# I2C_motor_driver.net
KiCad netlist of a schematic drawn in EAGLE
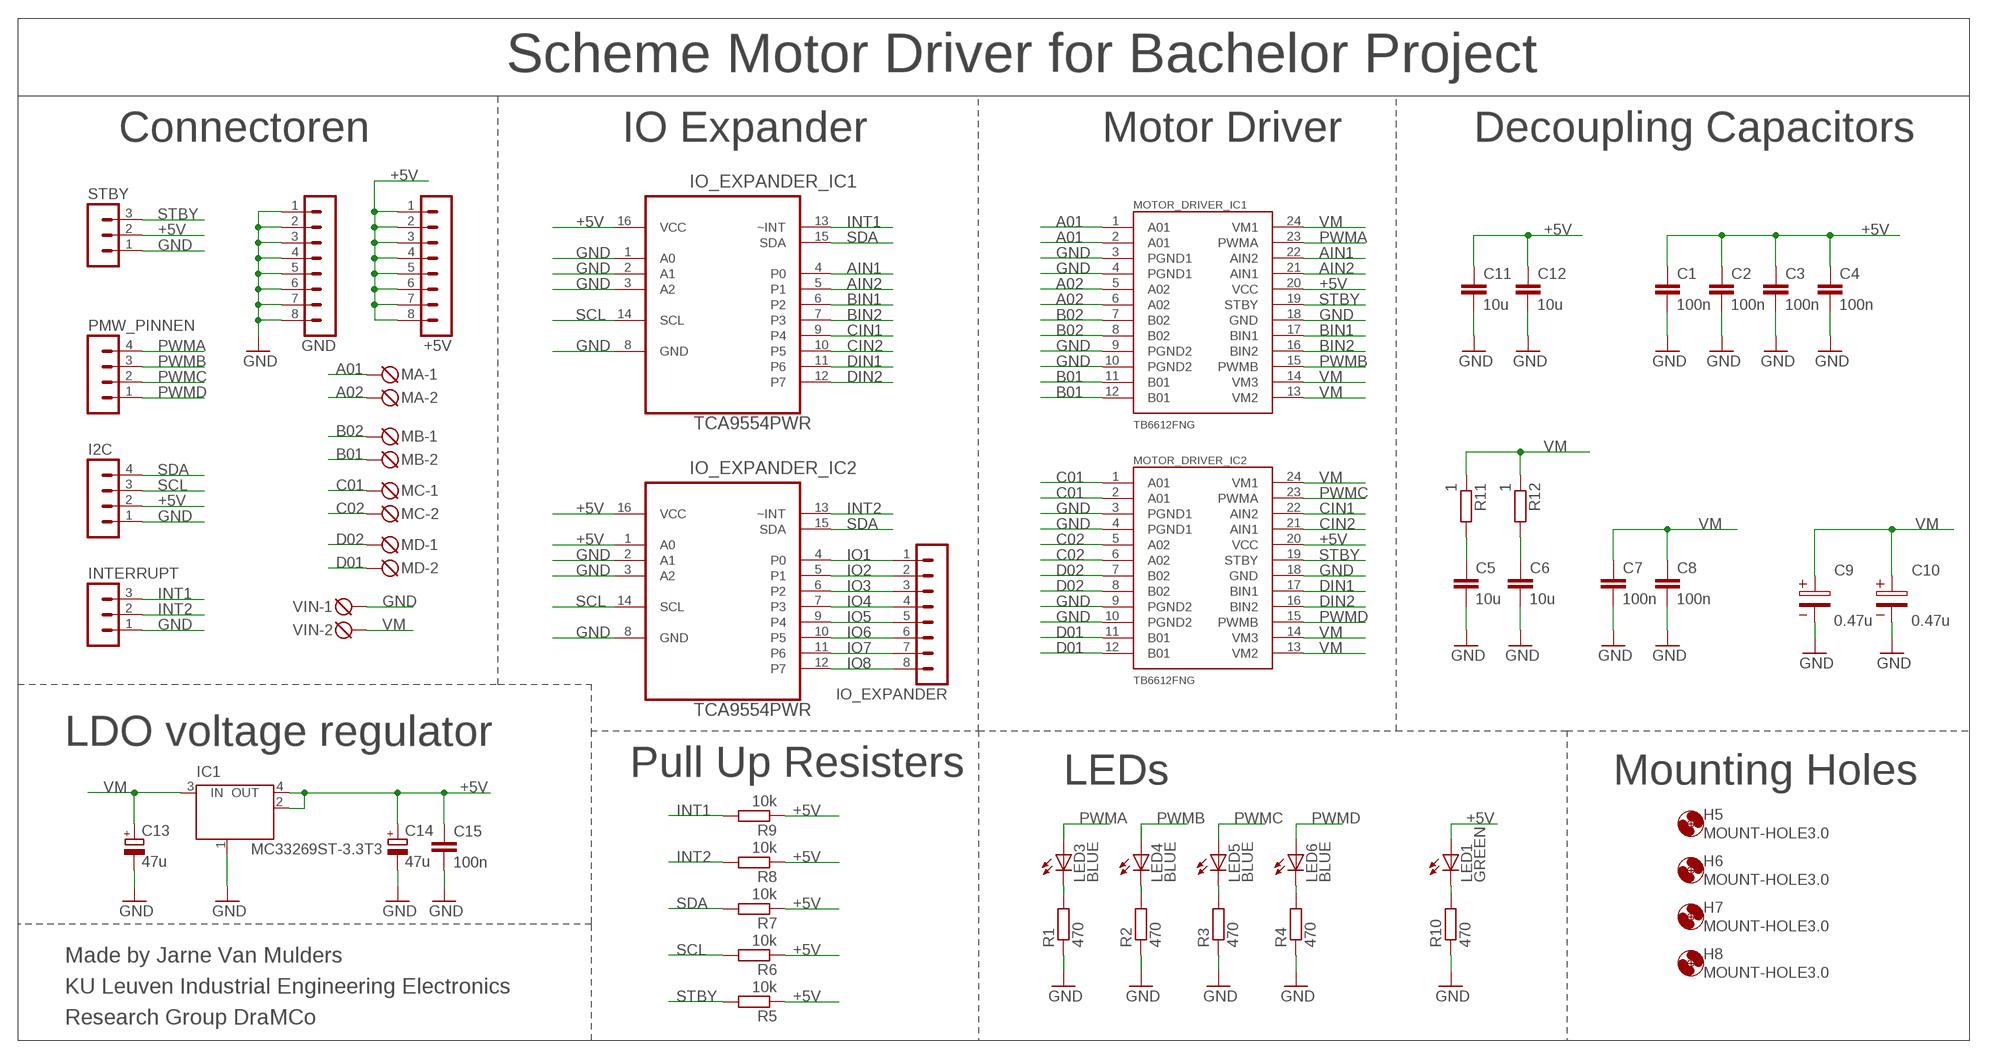
[diagram p0: schematic, sheet 1]

(export (version "E")
  (design (tool "Eeschema 10.0.6"))
  (components
    (comp (ref "+5V")
      (value "MA08-1")
      (footprint "eagle-import:MA08-1")
      (libsource (lib "eagle-import") (part "MA08-1"))
    )
    (comp (ref "C1")
      (value "100n")
      (footprint "eagle-import:C1206K")
      (libsource (lib "eagle-import") (part "C-EUC1206K"))
    )
    (comp (ref "C2")
      (value "100n")
      (footprint "eagle-import:C1206K")
      (libsource (lib "eagle-import") (part "C-EUC1206K"))
    )
    (comp (ref "C3")
      (value "100n")
      (footprint "eagle-import:C1206K")
      (libsource (lib "eagle-import") (part "C-EUC1206K"))
    )
    (comp (ref "C4")
      (value "100n")
      (footprint "eagle-import:C1206K")
      (libsource (lib "eagle-import") (part "C-EUC1206K"))
    )
    (comp (ref "C5")
      (value "10u")
      (footprint "eagle-import:C1206K")
      (libsource (lib "eagle-import") (part "C-EUC1206K"))
    )
    (comp (ref "C6")
      (value "10u")
      (footprint "eagle-import:C1206K")
      (libsource (lib "eagle-import") (part "C-EUC1206K"))
    )
    (comp (ref "C7")
      (value "100n")
      (footprint "eagle-import:C1206K")
      (libsource (lib "eagle-import") (part "C-EUC1206K"))
    )
    (comp (ref "C8")
      (value "100n")
      (footprint "eagle-import:C1206K")
      (libsource (lib "eagle-import") (part "C-EUC1206K"))
    )
    (comp (ref "C9")
      (value "0.47u")
      (footprint "eagle-import:2.6X1.6X1(BXCXA)")
      (libsource (lib "eagle-import") (part "WCAP-ASLI_865080740002_4X5,5"))
    )
    (comp (ref "C10")
      (value "0.47u")
      (footprint "eagle-import:2.6X1.6X1(BXCXA)")
      (libsource (lib "eagle-import") (part "WCAP-ASLI_865080740002_4X5,5"))
    )
    (comp (ref "C11")
      (value "10u")
      (footprint "eagle-import:C1206K")
      (libsource (lib "eagle-import") (part "C-EUC1206K"))
    )
    (comp (ref "C12")
      (value "10u")
      (footprint "eagle-import:C1206K")
      (libsource (lib "eagle-import") (part "C-EUC1206K"))
    )
    (comp (ref "C13")
      (value "47u")
      (footprint "eagle-import:PANASONIC_D")
      (libsource (lib "eagle-import") (part "CPOL-EUD"))
    )
    (comp (ref "C14")
      (value "47u")
      (footprint "eagle-import:PANASONIC_D")
      (libsource (lib "eagle-import") (part "CPOL-EUD"))
    )
    (comp (ref "C15")
      (value "100n")
      (footprint "eagle-import:C1206K")
      (libsource (lib "eagle-import") (part "C-EUC1206K"))
    )
    (comp (ref "GND")
      (value "MA08-1")
      (footprint "eagle-import:MA08-1")
      (libsource (lib "eagle-import") (part "MA08-1"))
    )
    (comp (ref "H5")
      (value "MOUNT-HOLE3.0")
      (footprint "eagle-import:3,0")
      (libsource (lib "eagle-import") (part "MOUNT-HOLE3.0"))
    )
    (comp (ref "H6")
      (value "MOUNT-HOLE3.0")
      (footprint "eagle-import:3,0")
      (libsource (lib "eagle-import") (part "MOUNT-HOLE3.0"))
    )
    (comp (ref "H7")
      (value "MOUNT-HOLE3.0")
      (footprint "eagle-import:3,0")
      (libsource (lib "eagle-import") (part "MOUNT-HOLE3.0"))
    )
    (comp (ref "H8")
      (value "MOUNT-HOLE3.0")
      (footprint "eagle-import:3,0")
      (libsource (lib "eagle-import") (part "MOUNT-HOLE3.0"))
    )
    (comp (ref "I2C")
      (value "MA04-1")
      (footprint "eagle-import:MA04-1")
      (libsource (lib "eagle-import") (part "MA04-1"))
    )
    (comp (ref "IC1")
      (value "MC33269ST-3.3T3")
      (footprint "eagle-import:SOT223")
      (libsource (lib "eagle-import") (part "MC33269ST-3.3T3"))
    )
    (comp (ref "INTERRUPT")
      (value "MA03-1")
      (footprint "eagle-import:MA03-1")
      (libsource (lib "eagle-import") (part "MA03-1"))
    )
    (comp (ref "IO_EXPANDER")
      (value "MA08-1")
      (footprint "eagle-import:MA08-1")
      (libsource (lib "eagle-import") (part "MA08-1"))
    )
    (comp (ref "IO_EXPANDER_IC1")
      (value "TCA9554PWR")
      (footprint "eagle-import:SOP65P640X120-16N")
      (fields (field (name "MF") "Texas Instruments"))
      (libsource (lib "eagle-import") (part "TCA9554PWR"))
    )
    (comp (ref "IO_EXPANDER_IC2")
      (value "TCA9554PWR")
      (footprint "eagle-import:SOP65P640X120-16N")
      (fields (field (name "MF") "Texas Instruments"))
      (libsource (lib "eagle-import") (part "TCA9554PWR"))
    )
    (comp (ref "LED1")
      (value "GREEN")
      (footprint "eagle-import:SML0805")
      (libsource (lib "eagle-import") (part "LEDSML0805"))
    )
    (comp (ref "LED3")
      (value "BLUE")
      (footprint "eagle-import:SML0805")
      (libsource (lib "eagle-import") (part "LEDSML0805"))
    )
    (comp (ref "LED4")
      (value "BLUE")
      (footprint "eagle-import:SML0805")
      (libsource (lib "eagle-import") (part "LEDSML0805"))
    )
    (comp (ref "LED5")
      (value "BLUE")
      (footprint "eagle-import:SML0805")
      (libsource (lib "eagle-import") (part "LEDSML0805"))
    )
    (comp (ref "LED6")
      (value "BLUE")
      (footprint "eagle-import:SML0805")
      (libsource (lib "eagle-import") (part "LEDSML0805"))
    )
    (comp (ref "MA")
      (value "DG3XX-02-5.0")
      (footprint "eagle-import:DG306-5.0-02P")
      (libsource (lib "eagle-import") (part "DG3XX-02-5.0"))
    )
    (comp (ref "MB")
      (value "DG3XX-02-5.0")
      (footprint "eagle-import:DG306-5.0-02P")
      (libsource (lib "eagle-import") (part "DG3XX-02-5.0"))
    )
    (comp (ref "MC")
      (value "DG3XX-02-5.0")
      (footprint "eagle-import:DG306-5.0-02P")
      (libsource (lib "eagle-import") (part "DG3XX-02-5.0"))
    )
    (comp (ref "MD")
      (value "DG3XX-02-5.0")
      (footprint "eagle-import:DG306-5.0-02P")
      (libsource (lib "eagle-import") (part "DG3XX-02-5.0"))
    )
    (comp (ref "MOTOR_DRIVER_IC1")
      (value "TB6612FNG")
      (footprint "eagle-import:SSOP24")
      (libsource (lib "eagle-import") (part "TB6612FNG"))
    )
    (comp (ref "MOTOR_DRIVER_IC2")
      (value "TB6612FNG")
      (footprint "eagle-import:SSOP24")
      (libsource (lib "eagle-import") (part "TB6612FNG"))
    )
    (comp (ref "PMW_PINNEN")
      (value "MA04-1")
      (footprint "eagle-import:MA04-1")
      (libsource (lib "eagle-import") (part "MA04-1"))
    )
    (comp (ref "R1")
      (value "470")
      (footprint "eagle-import:R1206")
      (libsource (lib "eagle-import") (part "R-EU_R1206"))
    )
    (comp (ref "R2")
      (value "470")
      (footprint "eagle-import:R1206")
      (libsource (lib "eagle-import") (part "R-EU_R1206"))
    )
    (comp (ref "R3")
      (value "470")
      (footprint "eagle-import:R1206")
      (libsource (lib "eagle-import") (part "R-EU_R1206"))
    )
    (comp (ref "R4")
      (value "470")
      (footprint "eagle-import:R1206")
      (libsource (lib "eagle-import") (part "R-EU_R1206"))
    )
    (comp (ref "R5")
      (value "10k")
      (footprint "eagle-import:R1206")
      (libsource (lib "eagle-import") (part "R-EU_R1206"))
    )
    (comp (ref "R6")
      (value "10k")
      (footprint "eagle-import:R1206")
      (libsource (lib "eagle-import") (part "R-EU_R1206"))
    )
    (comp (ref "R7")
      (value "10k")
      (footprint "eagle-import:R1206")
      (libsource (lib "eagle-import") (part "R-EU_R1206"))
    )
    (comp (ref "R8")
      (value "10k")
      (footprint "eagle-import:R1206")
      (libsource (lib "eagle-import") (part "R-EU_R1206"))
    )
    (comp (ref "R9")
      (value "10k")
      (footprint "eagle-import:R1206")
      (libsource (lib "eagle-import") (part "R-EU_R1206"))
    )
    (comp (ref "R10")
      (value "470")
      (footprint "eagle-import:R1206")
      (libsource (lib "eagle-import") (part "R-EU_R1206"))
    )
    (comp (ref "R11")
      (value "1")
      (footprint "eagle-import:R1206")
      (libsource (lib "eagle-import") (part "R-EU_R1206"))
    )
    (comp (ref "R12")
      (value "1")
      (footprint "eagle-import:R1206")
      (libsource (lib "eagle-import") (part "R-EU_R1206"))
    )
    (comp (ref "STBY")
      (value "MA03-1")
      (footprint "eagle-import:MA03-1")
      (libsource (lib "eagle-import") (part "MA03-1"))
    )
    (comp (ref "VIN")
      (value "DG3XX-02-5.0")
      (footprint "eagle-import:DG306-5.0-02P")
      (libsource (lib "eagle-import") (part "DG3XX-02-5.0"))
    )
  )
  (nets
    (net (code "1") (name "/+5V") (class "Default")
      (node (ref "+5V") (pin "1") (pinfunction "1_1") (pintype "passive"))
      (node (ref "+5V") (pin "2") (pinfunction "2_2") (pintype "passive"))
      (node (ref "+5V") (pin "3") (pinfunction "3_3") (pintype "passive"))
      (node (ref "+5V") (pin "4") (pinfunction "4_4") (pintype "passive"))
      (node (ref "+5V") (pin "5") (pinfunction "5_5") (pintype "passive"))
      (node (ref "+5V") (pin "6") (pinfunction "6_6") (pintype "passive"))
      (node (ref "+5V") (pin "7") (pinfunction "7_7") (pintype "passive"))
      (node (ref "+5V") (pin "8") (pinfunction "8_8") (pintype "passive"))
      (node (ref "C1") (pin "1") (pinfunction "1_1") (pintype "passive"))
      (node (ref "C11") (pin "1") (pinfunction "1_1") (pintype "passive"))
      (node (ref "C12") (pin "1") (pinfunction "1_1") (pintype "passive"))
      (node (ref "C14") (pin "+") (pinfunction "+_+") (pintype "passive"))
      (node (ref "C15") (pin "1") (pinfunction "1_1") (pintype "passive"))
      (node (ref "C2") (pin "1") (pinfunction "1_1") (pintype "passive"))
      (node (ref "C3") (pin "1") (pinfunction "1_1") (pintype "passive"))
      (node (ref "C4") (pin "1") (pinfunction "1_1") (pintype "passive"))
      (node (ref "I2C") (pin "2") (pinfunction "2_2") (pintype "passive"))
      (node (ref "IC1") (pin "2") (pinfunction "OUT_2") (pintype "passive"))
      (node (ref "IC1") (pin "4") (pinfunction "OUT_4") (pintype "passive"))
      (node (ref "IO_EXPANDER_IC1") (pin "16") (pinfunction "VCC_16") (pintype "power_in"))
      (node (ref "IO_EXPANDER_IC2") (pin "1") (pinfunction "A0_1") (pintype "input"))
      (node (ref "IO_EXPANDER_IC2") (pin "16") (pinfunction "VCC_16") (pintype "power_in"))
      (node (ref "LED1") (pin "A") (pinfunction "A_A") (pintype "passive"))
      (node (ref "MOTOR_DRIVER_IC1") (pin "20") (pinfunction "VCC_20") (pintype "bidirectional"))
      (node (ref "MOTOR_DRIVER_IC2") (pin "20") (pinfunction "VCC_20") (pintype "bidirectional"))
      (node (ref "R5") (pin "1") (pinfunction "1_1") (pintype "passive"))
      (node (ref "R6") (pin "1") (pinfunction "1_1") (pintype "passive"))
      (node (ref "R7") (pin "1") (pinfunction "1_1") (pintype "passive"))
      (node (ref "R8") (pin "1") (pinfunction "1_1") (pintype "passive"))
      (node (ref "R9") (pin "1") (pinfunction "1_1") (pintype "passive"))
      (node (ref "STBY") (pin "2") (pinfunction "2_2") (pintype "passive"))
    )
    (net (code "2") (name "/A01") (class "Default")
      (node (ref "MA") (pin "1") (pinfunction "KL_1") (pintype "passive"))
      (node (ref "MOTOR_DRIVER_IC1") (pin "1") (pinfunction "A01_1") (pintype "bidirectional"))
      (node (ref "MOTOR_DRIVER_IC1") (pin "2") (pinfunction "A01_2") (pintype "bidirectional"))
    )
    (net (code "3") (name "/A02") (class "Default")
      (node (ref "MA") (pin "2") (pinfunction "KL_2") (pintype "passive"))
      (node (ref "MOTOR_DRIVER_IC1") (pin "5") (pinfunction "A02_5") (pintype "bidirectional"))
      (node (ref "MOTOR_DRIVER_IC1") (pin "6") (pinfunction "A02_6") (pintype "bidirectional"))
    )
    (net (code "4") (name "/AIN1") (class "Default")
      (node (ref "IO_EXPANDER_IC1") (pin "4") (pinfunction "P0_4") (pintype "bidirectional"))
      (node (ref "MOTOR_DRIVER_IC1") (pin "22") (pinfunction "AIN2_22") (pintype "bidirectional"))
    )
    (net (code "5") (name "/AIN2") (class "Default")
      (node (ref "IO_EXPANDER_IC1") (pin "5") (pinfunction "P1_5") (pintype "bidirectional"))
      (node (ref "MOTOR_DRIVER_IC1") (pin "21") (pinfunction "AIN1_21") (pintype "bidirectional"))
    )
    (net (code "6") (name "/B01") (class "Default")
      (node (ref "MB") (pin "2") (pinfunction "KL_2") (pintype "passive"))
      (node (ref "MOTOR_DRIVER_IC1") (pin "11") (pinfunction "B01_11") (pintype "bidirectional"))
      (node (ref "MOTOR_DRIVER_IC1") (pin "12") (pinfunction "B01_12") (pintype "bidirectional"))
    )
    (net (code "7") (name "/B02") (class "Default")
      (node (ref "MB") (pin "1") (pinfunction "KL_1") (pintype "passive"))
      (node (ref "MOTOR_DRIVER_IC1") (pin "7") (pinfunction "B02_7") (pintype "bidirectional"))
      (node (ref "MOTOR_DRIVER_IC1") (pin "8") (pinfunction "B02_8") (pintype "bidirectional"))
    )
    (net (code "8") (name "/BIN1") (class "Default")
      (node (ref "IO_EXPANDER_IC1") (pin "6") (pinfunction "P2_6") (pintype "bidirectional"))
      (node (ref "MOTOR_DRIVER_IC1") (pin "17") (pinfunction "BIN1_17") (pintype "bidirectional"))
    )
    (net (code "9") (name "/BIN2") (class "Default")
      (node (ref "IO_EXPANDER_IC1") (pin "7") (pinfunction "P3_7") (pintype "bidirectional"))
      (node (ref "MOTOR_DRIVER_IC1") (pin "16") (pinfunction "BIN2_16") (pintype "bidirectional"))
    )
    (net (code "10") (name "/C01") (class "Default")
      (node (ref "MC") (pin "1") (pinfunction "KL_1") (pintype "passive"))
      (node (ref "MOTOR_DRIVER_IC2") (pin "1") (pinfunction "A01_1") (pintype "bidirectional"))
      (node (ref "MOTOR_DRIVER_IC2") (pin "2") (pinfunction "A01_2") (pintype "bidirectional"))
    )
    (net (code "11") (name "/C02") (class "Default")
      (node (ref "MC") (pin "2") (pinfunction "KL_2") (pintype "passive"))
      (node (ref "MOTOR_DRIVER_IC2") (pin "5") (pinfunction "A02_5") (pintype "bidirectional"))
      (node (ref "MOTOR_DRIVER_IC2") (pin "6") (pinfunction "A02_6") (pintype "bidirectional"))
    )
    (net (code "12") (name "/CIN1") (class "Default")
      (node (ref "IO_EXPANDER_IC1") (pin "9") (pinfunction "P4_9") (pintype "bidirectional"))
      (node (ref "MOTOR_DRIVER_IC2") (pin "22") (pinfunction "AIN2_22") (pintype "bidirectional"))
    )
    (net (code "13") (name "/CIN2") (class "Default")
      (node (ref "IO_EXPANDER_IC1") (pin "10") (pinfunction "P5_10") (pintype "bidirectional"))
      (node (ref "MOTOR_DRIVER_IC2") (pin "21") (pinfunction "AIN1_21") (pintype "bidirectional"))
    )
    (net (code "14") (name "/D01") (class "Default")
      (node (ref "MD") (pin "2") (pinfunction "KL_2") (pintype "passive"))
      (node (ref "MOTOR_DRIVER_IC2") (pin "11") (pinfunction "B01_11") (pintype "bidirectional"))
      (node (ref "MOTOR_DRIVER_IC2") (pin "12") (pinfunction "B01_12") (pintype "bidirectional"))
    )
    (net (code "15") (name "/D02") (class "Default")
      (node (ref "MD") (pin "1") (pinfunction "KL_1") (pintype "passive"))
      (node (ref "MOTOR_DRIVER_IC2") (pin "7") (pinfunction "B02_7") (pintype "bidirectional"))
      (node (ref "MOTOR_DRIVER_IC2") (pin "8") (pinfunction "B02_8") (pintype "bidirectional"))
    )
    (net (code "16") (name "/DIN1") (class "Default")
      (node (ref "IO_EXPANDER_IC1") (pin "11") (pinfunction "P6_11") (pintype "bidirectional"))
      (node (ref "MOTOR_DRIVER_IC2") (pin "17") (pinfunction "BIN1_17") (pintype "bidirectional"))
    )
    (net (code "17") (name "/DIN2") (class "Default")
      (node (ref "IO_EXPANDER_IC1") (pin "12") (pinfunction "P7_12") (pintype "bidirectional"))
      (node (ref "MOTOR_DRIVER_IC2") (pin "16") (pinfunction "BIN2_16") (pintype "bidirectional"))
    )
    (net (code "18") (name "/INT1") (class "Default")
      (node (ref "INTERRUPT") (pin "3") (pinfunction "3_3") (pintype "passive"))
      (node (ref "IO_EXPANDER_IC1") (pin "13") (pinfunction "~{INT}_13") (pintype "output"))
      (node (ref "R9") (pin "2") (pinfunction "2_2") (pintype "passive"))
    )
    (net (code "19") (name "/INT2") (class "Default")
      (node (ref "INTERRUPT") (pin "2") (pinfunction "2_2") (pintype "passive"))
      (node (ref "IO_EXPANDER_IC2") (pin "13") (pinfunction "~{INT}_13") (pintype "output"))
      (node (ref "R8") (pin "2") (pinfunction "2_2") (pintype "passive"))
    )
    (net (code "20") (name "/IO1") (class "Default")
      (node (ref "IO_EXPANDER") (pin "1") (pinfunction "1_1") (pintype "passive"))
      (node (ref "IO_EXPANDER_IC2") (pin "4") (pinfunction "P0_4") (pintype "bidirectional"))
    )
    (net (code "21") (name "/IO2") (class "Default")
      (node (ref "IO_EXPANDER") (pin "2") (pinfunction "2_2") (pintype "passive"))
      (node (ref "IO_EXPANDER_IC2") (pin "5") (pinfunction "P1_5") (pintype "bidirectional"))
    )
    (net (code "22") (name "/IO3") (class "Default")
      (node (ref "IO_EXPANDER") (pin "3") (pinfunction "3_3") (pintype "passive"))
      (node (ref "IO_EXPANDER_IC2") (pin "6") (pinfunction "P2_6") (pintype "bidirectional"))
    )
    (net (code "23") (name "/IO4") (class "Default")
      (node (ref "IO_EXPANDER") (pin "4") (pinfunction "4_4") (pintype "passive"))
      (node (ref "IO_EXPANDER_IC2") (pin "7") (pinfunction "P3_7") (pintype "bidirectional"))
    )
    (net (code "24") (name "/IO5") (class "Default")
      (node (ref "IO_EXPANDER") (pin "5") (pinfunction "5_5") (pintype "passive"))
      (node (ref "IO_EXPANDER_IC2") (pin "9") (pinfunction "P4_9") (pintype "bidirectional"))
    )
    (net (code "25") (name "/IO6") (class "Default")
      (node (ref "IO_EXPANDER") (pin "6") (pinfunction "6_6") (pintype "passive"))
      (node (ref "IO_EXPANDER_IC2") (pin "10") (pinfunction "P5_10") (pintype "bidirectional"))
    )
    (net (code "26") (name "/IO7") (class "Default")
      (node (ref "IO_EXPANDER") (pin "7") (pinfunction "7_7") (pintype "passive"))
      (node (ref "IO_EXPANDER_IC2") (pin "11") (pinfunction "P6_11") (pintype "bidirectional"))
    )
    (net (code "27") (name "/IO8") (class "Default")
      (node (ref "IO_EXPANDER") (pin "8") (pinfunction "8_8") (pintype "passive"))
      (node (ref "IO_EXPANDER_IC2") (pin "12") (pinfunction "P7_12") (pintype "bidirectional"))
    )
    (net (code "28") (name "/PWMA") (class "Default")
      (node (ref "LED3") (pin "A") (pinfunction "A_A") (pintype "passive"))
      (node (ref "MOTOR_DRIVER_IC1") (pin "23") (pinfunction "PWMA_23") (pintype "bidirectional"))
      (node (ref "PMW_PINNEN") (pin "4") (pinfunction "4_4") (pintype "passive"))
    )
    (net (code "29") (name "/PWMB") (class "Default")
      (node (ref "LED4") (pin "A") (pinfunction "A_A") (pintype "passive"))
      (node (ref "MOTOR_DRIVER_IC1") (pin "15") (pinfunction "PWMB_15") (pintype "bidirectional"))
      (node (ref "PMW_PINNEN") (pin "3") (pinfunction "3_3") (pintype "passive"))
    )
    (net (code "30") (name "/PWMC") (class "Default")
      (node (ref "LED5") (pin "A") (pinfunction "A_A") (pintype "passive"))
      (node (ref "MOTOR_DRIVER_IC2") (pin "23") (pinfunction "PWMA_23") (pintype "bidirectional"))
      (node (ref "PMW_PINNEN") (pin "2") (pinfunction "2_2") (pintype "passive"))
    )
    (net (code "31") (name "/PWMD") (class "Default")
      (node (ref "LED6") (pin "A") (pinfunction "A_A") (pintype "passive"))
      (node (ref "MOTOR_DRIVER_IC2") (pin "15") (pinfunction "PWMB_15") (pintype "bidirectional"))
      (node (ref "PMW_PINNEN") (pin "1") (pinfunction "1_1") (pintype "passive"))
    )
    (net (code "32") (name "/SCL") (class "Default")
      (node (ref "I2C") (pin "3") (pinfunction "3_3") (pintype "passive"))
      (node (ref "IO_EXPANDER_IC1") (pin "14") (pinfunction "SCL_14") (pintype "input"))
      (node (ref "IO_EXPANDER_IC2") (pin "14") (pinfunction "SCL_14") (pintype "input"))
      (node (ref "R6") (pin "2") (pinfunction "2_2") (pintype "passive"))
    )
    (net (code "33") (name "/SDA") (class "Default")
      (node (ref "I2C") (pin "4") (pinfunction "4_4") (pintype "passive"))
      (node (ref "IO_EXPANDER_IC1") (pin "15") (pinfunction "SDA_15") (pintype "bidirectional"))
      (node (ref "IO_EXPANDER_IC2") (pin "15") (pinfunction "SDA_15") (pintype "bidirectional"))
      (node (ref "R7") (pin "2") (pinfunction "2_2") (pintype "passive"))
    )
    (net (code "34") (name "/STBY") (class "Default")
      (node (ref "MOTOR_DRIVER_IC1") (pin "19") (pinfunction "STBY_19") (pintype "bidirectional"))
      (node (ref "MOTOR_DRIVER_IC2") (pin "19") (pinfunction "STBY_19") (pintype "bidirectional"))
      (node (ref "R5") (pin "2") (pinfunction "2_2") (pintype "passive"))
      (node (ref "STBY") (pin "3") (pinfunction "3_3") (pintype "passive"))
    )
    (net (code "35") (name "/VM") (class "Default")
      (node (ref "C10") (pin "1") (pinfunction "1_1") (pintype "passive"))
      (node (ref "C13") (pin "+") (pinfunction "+_+") (pintype "passive"))
      (node (ref "C7") (pin "1") (pinfunction "1_1") (pintype "passive"))
      (node (ref "C8") (pin "1") (pinfunction "1_1") (pintype "passive"))
      (node (ref "C9") (pin "1") (pinfunction "1_1") (pintype "passive"))
      (node (ref "IC1") (pin "3") (pinfunction "IN_3") (pintype "input"))
      (node (ref "MOTOR_DRIVER_IC1") (pin "13") (pinfunction "VM2_13") (pintype "bidirectional"))
      (node (ref "MOTOR_DRIVER_IC1") (pin "14") (pinfunction "VM3_14") (pintype "bidirectional"))
      (node (ref "MOTOR_DRIVER_IC1") (pin "24") (pinfunction "VM1_24") (pintype "bidirectional"))
      (node (ref "MOTOR_DRIVER_IC2") (pin "13") (pinfunction "VM2_13") (pintype "bidirectional"))
      (node (ref "MOTOR_DRIVER_IC2") (pin "14") (pinfunction "VM3_14") (pintype "bidirectional"))
      (node (ref "MOTOR_DRIVER_IC2") (pin "24") (pinfunction "VM1_24") (pintype "bidirectional"))
      (node (ref "R11") (pin "1") (pinfunction "1_1") (pintype "passive"))
      (node (ref "R12") (pin "1") (pinfunction "1_1") (pintype "passive"))
      (node (ref "VIN") (pin "2") (pinfunction "KL_2") (pintype "passive"))
    )
    (net (code "36") (name "GND") (class "Default")
      (node (ref "C1") (pin "2") (pinfunction "2_2") (pintype "passive"))
      (node (ref "C10") (pin "2") (pinfunction "2_2") (pintype "passive"))
      (node (ref "C11") (pin "2") (pinfunction "2_2") (pintype "passive"))
      (node (ref "C12") (pin "2") (pinfunction "2_2") (pintype "passive"))
      (node (ref "C13") (pin "-") (pinfunction "-_-") (pintype "passive"))
      (node (ref "C14") (pin "-") (pinfunction "-_-") (pintype "passive"))
      (node (ref "C15") (pin "2") (pinfunction "2_2") (pintype "passive"))
      (node (ref "C2") (pin "2") (pinfunction "2_2") (pintype "passive"))
      (node (ref "C3") (pin "2") (pinfunction "2_2") (pintype "passive"))
      (node (ref "C4") (pin "2") (pinfunction "2_2") (pintype "passive"))
      (node (ref "C5") (pin "2") (pinfunction "2_2") (pintype "passive"))
      (node (ref "C6") (pin "2") (pinfunction "2_2") (pintype "passive"))
      (node (ref "C7") (pin "2") (pinfunction "2_2") (pintype "passive"))
      (node (ref "C8") (pin "2") (pinfunction "2_2") (pintype "passive"))
      (node (ref "C9") (pin "2") (pinfunction "2_2") (pintype "passive"))
      (node (ref "GND") (pin "1") (pinfunction "1_1") (pintype "passive"))
      (node (ref "GND") (pin "2") (pinfunction "2_2") (pintype "passive"))
      (node (ref "GND") (pin "3") (pinfunction "3_3") (pintype "passive"))
      (node (ref "GND") (pin "4") (pinfunction "4_4") (pintype "passive"))
      (node (ref "GND") (pin "5") (pinfunction "5_5") (pintype "passive"))
      (node (ref "GND") (pin "6") (pinfunction "6_6") (pintype "passive"))
      (node (ref "GND") (pin "7") (pinfunction "7_7") (pintype "passive"))
      (node (ref "GND") (pin "8") (pinfunction "8_8") (pintype "passive"))
      (node (ref "I2C") (pin "1") (pinfunction "1_1") (pintype "passive"))
      (node (ref "IC1") (pin "1") (pinfunction "GND/ADJ_1") (pintype "input"))
      (node (ref "INTERRUPT") (pin "1") (pinfunction "1_1") (pintype "passive"))
      (node (ref "IO_EXPANDER_IC1") (pin "1") (pinfunction "A0_1") (pintype "input"))
      (node (ref "IO_EXPANDER_IC1") (pin "2") (pinfunction "A1_2") (pintype "input"))
      (node (ref "IO_EXPANDER_IC1") (pin "3") (pinfunction "A2_3") (pintype "input"))
      (node (ref "IO_EXPANDER_IC1") (pin "8") (pinfunction "GND_8") (pintype "passive"))
      (node (ref "IO_EXPANDER_IC2") (pin "2") (pinfunction "A1_2") (pintype "input"))
      (node (ref "IO_EXPANDER_IC2") (pin "3") (pinfunction "A2_3") (pintype "input"))
      (node (ref "IO_EXPANDER_IC2") (pin "8") (pinfunction "GND_8") (pintype "passive"))
      (node (ref "MOTOR_DRIVER_IC1") (pin "10") (pinfunction "PGND2_10") (pintype "bidirectional"))
      (node (ref "MOTOR_DRIVER_IC1") (pin "18") (pinfunction "GND_18") (pintype "bidirectional"))
      (node (ref "MOTOR_DRIVER_IC1") (pin "3") (pinfunction "PGND1_3") (pintype "bidirectional"))
      (node (ref "MOTOR_DRIVER_IC1") (pin "4") (pinfunction "PGND1_4") (pintype "bidirectional"))
      (node (ref "MOTOR_DRIVER_IC1") (pin "9") (pinfunction "PGND2_9") (pintype "bidirectional"))
      (node (ref "MOTOR_DRIVER_IC2") (pin "10") (pinfunction "PGND2_10") (pintype "bidirectional"))
      (node (ref "MOTOR_DRIVER_IC2") (pin "18") (pinfunction "GND_18") (pintype "bidirectional"))
      (node (ref "MOTOR_DRIVER_IC2") (pin "3") (pinfunction "PGND1_3") (pintype "bidirectional"))
      (node (ref "MOTOR_DRIVER_IC2") (pin "4") (pinfunction "PGND1_4") (pintype "bidirectional"))
      (node (ref "MOTOR_DRIVER_IC2") (pin "9") (pinfunction "PGND2_9") (pintype "bidirectional"))
      (node (ref "R1") (pin "1") (pinfunction "1_1") (pintype "passive"))
      (node (ref "R10") (pin "1") (pinfunction "1_1") (pintype "passive"))
      (node (ref "R2") (pin "1") (pinfunction "1_1") (pintype "passive"))
      (node (ref "R3") (pin "1") (pinfunction "1_1") (pintype "passive"))
      (node (ref "R4") (pin "1") (pinfunction "1_1") (pintype "passive"))
      (node (ref "STBY") (pin "1") (pinfunction "1_1") (pintype "passive"))
      (node (ref "VIN") (pin "1") (pinfunction "KL_1") (pintype "passive"))
    )
    (net (code "37") (name "Net-(C5-Pad1)") (class "Default")
      (node (ref "C5") (pin "1") (pinfunction "1_1") (pintype "passive"))
      (node (ref "R11") (pin "2") (pinfunction "2_2") (pintype "passive"))
    )
    (net (code "38") (name "Net-(C6-Pad1)") (class "Default")
      (node (ref "C6") (pin "1") (pinfunction "1_1") (pintype "passive"))
      (node (ref "R12") (pin "2") (pinfunction "2_2") (pintype "passive"))
    )
    (net (code "39") (name "Net-(LED1-PadC)") (class "Default")
      (node (ref "LED1") (pin "C") (pinfunction "C_C") (pintype "passive"))
      (node (ref "R10") (pin "2") (pinfunction "2_2") (pintype "passive"))
    )
    (net (code "40") (name "Net-(LED3-PadC)") (class "Default")
      (node (ref "LED3") (pin "C") (pinfunction "C_C") (pintype "passive"))
      (node (ref "R1") (pin "2") (pinfunction "2_2") (pintype "passive"))
    )
    (net (code "41") (name "Net-(LED4-PadC)") (class "Default")
      (node (ref "LED4") (pin "C") (pinfunction "C_C") (pintype "passive"))
      (node (ref "R2") (pin "2") (pinfunction "2_2") (pintype "passive"))
    )
    (net (code "42") (name "Net-(LED5-PadC)") (class "Default")
      (node (ref "LED5") (pin "C") (pinfunction "C_C") (pintype "passive"))
      (node (ref "R3") (pin "2") (pinfunction "2_2") (pintype "passive"))
    )
    (net (code "43") (name "Net-(LED6-PadC)") (class "Default")
      (node (ref "LED6") (pin "C") (pinfunction "C_C") (pintype "passive"))
      (node (ref "R4") (pin "2") (pinfunction "2_2") (pintype "passive"))
    )
  )
)
